# A1-_Ricky_A-Schematic.net
KiCad netlist of a schematic drawn in EAGLE
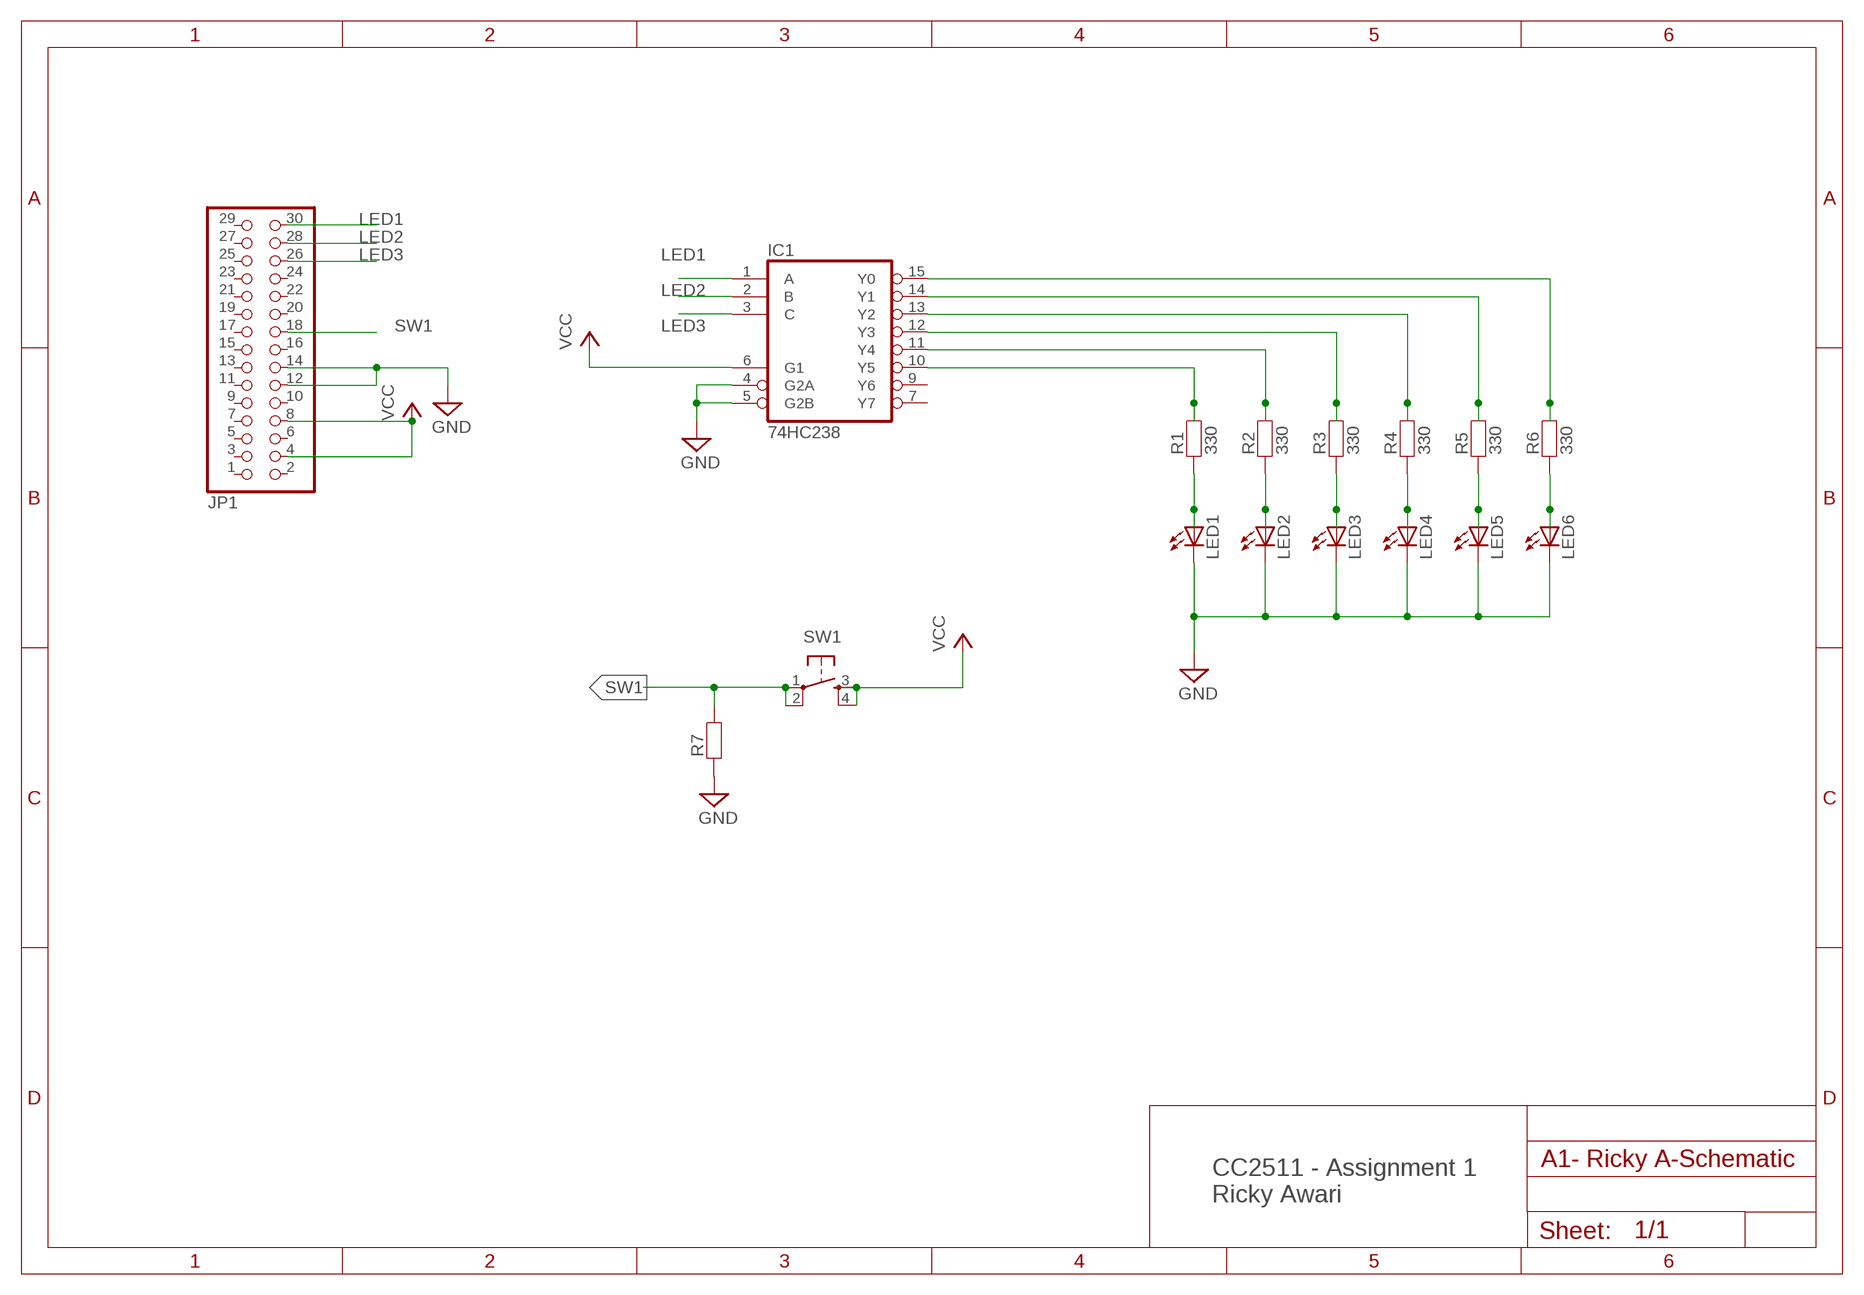
[diagram p0: schematic, sheet 1]

(export (version "E")
  (design (tool "Eeschema 10.0.6"))
  (components
    (comp (ref "IC1")
      (value "74HC238")
      (footprint "eagle-import:DIL16")
      (libsource (lib "eagle-import") (part "74138NHC"))
    )
    (comp (ref "JP1")
      (value "PINHD-2X15")
      (footprint "eagle-import:2X15")
      (libsource (lib "eagle-import") (part "PINHD-2X15"))
    )
    (comp (ref "LED1")
      (value "LED-5MM")
      (footprint "eagle-import:LED-5MM")
      (libsource (lib "eagle-import") (part "LED-5MM"))
    )
    (comp (ref "LED2")
      (value "LED-5MM")
      (footprint "eagle-import:LED-5MM")
      (libsource (lib "eagle-import") (part "LED-5MM"))
    )
    (comp (ref "LED3")
      (value "LED-5MM")
      (footprint "eagle-import:LED-5MM")
      (libsource (lib "eagle-import") (part "LED-5MM"))
    )
    (comp (ref "LED4")
      (value "LED-5MM")
      (footprint "eagle-import:LED-5MM")
      (libsource (lib "eagle-import") (part "LED-5MM"))
    )
    (comp (ref "LED5")
      (value "LED-5MM")
      (footprint "eagle-import:LED-5MM")
      (libsource (lib "eagle-import") (part "LED-5MM"))
    )
    (comp (ref "LED6")
      (value "LED-5MM")
      (footprint "eagle-import:LED-5MM")
      (libsource (lib "eagle-import") (part "LED-5MM"))
    )
    (comp (ref "R1")
      (value "330")
      (footprint "eagle-import:AXIAL-0.4")
      (libsource (lib "eagle-import") (part "RESISTOR-AXIAL-0.4"))
    )
    (comp (ref "R2")
      (value "330")
      (footprint "eagle-import:AXIAL-0.4")
      (libsource (lib "eagle-import") (part "RESISTOR-AXIAL-0.4"))
    )
    (comp (ref "R3")
      (value "330")
      (footprint "eagle-import:AXIAL-0.4")
      (libsource (lib "eagle-import") (part "RESISTOR-AXIAL-0.4"))
    )
    (comp (ref "R4")
      (value "330")
      (footprint "eagle-import:AXIAL-0.4")
      (libsource (lib "eagle-import") (part "RESISTOR-AXIAL-0.4"))
    )
    (comp (ref "R5")
      (value "330")
      (footprint "eagle-import:AXIAL-0.4")
      (libsource (lib "eagle-import") (part "RESISTOR-AXIAL-0.4"))
    )
    (comp (ref "R6")
      (value "330")
      (footprint "eagle-import:AXIAL-0.4")
      (libsource (lib "eagle-import") (part "RESISTOR-AXIAL-0.4"))
    )
    (comp (ref "R7")
      (value "RESISTOR-AXIAL-0.4")
      (footprint "eagle-import:AXIAL-0.4")
      (libsource (lib "eagle-import") (part "RESISTOR-AXIAL-0.4"))
    )
    (comp (ref "SW1")
      (value "TAC_SWITCHPTH")
      (footprint "eagle-import:TACTILE-PTH")
      (libsource (lib "eagle-import") (part "TAC_SWITCHPTH"))
    )
  )
  (nets
    (net (code "1") (name "/LED1") (class "Default")
      (node (ref "IC1") (pin "1") (pinfunction "A_1") (pintype "input"))
      (node (ref "JP1") (pin "30") (pinfunction "30_30") (pintype "passive"))
    )
    (net (code "2") (name "/LED2") (class "Default")
      (node (ref "IC1") (pin "2") (pinfunction "B_2") (pintype "input"))
      (node (ref "JP1") (pin "28") (pinfunction "28_28") (pintype "passive"))
    )
    (net (code "3") (name "/LED3") (class "Default")
      (node (ref "IC1") (pin "3") (pinfunction "C_3") (pintype "input"))
      (node (ref "JP1") (pin "26") (pinfunction "26_26") (pintype "passive"))
    )
    (net (code "4") (name "GND") (class "Default")
      (node (ref "IC1") (pin "4") (pinfunction "G2A_4") (pintype "input"))
      (node (ref "IC1") (pin "5") (pinfunction "G2B_5") (pintype "input"))
      (node (ref "JP1") (pin "12") (pinfunction "12_12") (pintype "passive"))
      (node (ref "JP1") (pin "14") (pinfunction "14_14") (pintype "passive"))
      (node (ref "LED1") (pin "C") (pinfunction "C_C") (pintype "passive"))
      (node (ref "LED2") (pin "C") (pinfunction "C_C") (pintype "passive"))
      (node (ref "LED3") (pin "C") (pinfunction "C_C") (pintype "passive"))
      (node (ref "LED4") (pin "C") (pinfunction "C_C") (pintype "passive"))
      (node (ref "LED5") (pin "C") (pinfunction "C_C") (pintype "passive"))
      (node (ref "LED6") (pin "C") (pinfunction "C_C") (pintype "passive"))
      (node (ref "R7") (pin "P$1") (pinfunction "1_P$1") (pintype "passive"))
    )
    (net (code "5") (name "Net-(IC1A-Y0)") (class "Default")
      (node (ref "IC1") (pin "15") (pinfunction "Y0_15") (pintype "output"))
      (node (ref "R6") (pin "P$2") (pinfunction "2_P$2") (pintype "passive"))
    )
    (net (code "6") (name "Net-(IC1A-Y1)") (class "Default")
      (node (ref "IC1") (pin "14") (pinfunction "Y1_14") (pintype "output"))
      (node (ref "R5") (pin "P$2") (pinfunction "2_P$2") (pintype "passive"))
    )
    (net (code "7") (name "Net-(IC1A-Y2)") (class "Default")
      (node (ref "IC1") (pin "13") (pinfunction "Y2_13") (pintype "output"))
      (node (ref "R4") (pin "P$2") (pinfunction "2_P$2") (pintype "passive"))
    )
    (net (code "8") (name "Net-(IC1A-Y3)") (class "Default")
      (node (ref "IC1") (pin "12") (pinfunction "Y3_12") (pintype "output"))
      (node (ref "R3") (pin "P$2") (pinfunction "2_P$2") (pintype "passive"))
    )
    (net (code "9") (name "Net-(IC1A-Y4)") (class "Default")
      (node (ref "IC1") (pin "11") (pinfunction "Y4_11") (pintype "output"))
      (node (ref "R2") (pin "P$2") (pinfunction "2_P$2") (pintype "passive"))
    )
    (net (code "10") (name "Net-(IC1A-Y5)") (class "Default")
      (node (ref "IC1") (pin "10") (pinfunction "Y5_10") (pintype "output"))
      (node (ref "R1") (pin "P$2") (pinfunction "2_P$2") (pintype "passive"))
    )
    (net (code "11") (name "Net-(R1-1)") (class "Default")
      (node (ref "LED1") (pin "A") (pinfunction "A_A") (pintype "passive"))
      (node (ref "R1") (pin "P$1") (pinfunction "1_P$1") (pintype "passive"))
    )
    (net (code "12") (name "Net-(R2-1)") (class "Default")
      (node (ref "LED2") (pin "A") (pinfunction "A_A") (pintype "passive"))
      (node (ref "R2") (pin "P$1") (pinfunction "1_P$1") (pintype "passive"))
    )
    (net (code "13") (name "Net-(R3-1)") (class "Default")
      (node (ref "LED3") (pin "A") (pinfunction "A_A") (pintype "passive"))
      (node (ref "R3") (pin "P$1") (pinfunction "1_P$1") (pintype "passive"))
    )
    (net (code "14") (name "Net-(R4-1)") (class "Default")
      (node (ref "LED4") (pin "A") (pinfunction "A_A") (pintype "passive"))
      (node (ref "R4") (pin "P$1") (pinfunction "1_P$1") (pintype "passive"))
    )
    (net (code "15") (name "Net-(R5-1)") (class "Default")
      (node (ref "LED5") (pin "A") (pinfunction "A_A") (pintype "passive"))
      (node (ref "R5") (pin "P$1") (pinfunction "1_P$1") (pintype "passive"))
    )
    (net (code "16") (name "Net-(R6-1)") (class "Default")
      (node (ref "LED6") (pin "A") (pinfunction "A_A") (pintype "passive"))
      (node (ref "R6") (pin "P$1") (pinfunction "1_P$1") (pintype "passive"))
    )
    (net (code "17") (name "SW1") (class "Default")
      (node (ref "JP1") (pin "18") (pinfunction "18_18") (pintype "passive"))
      (node (ref "R7") (pin "P$2") (pinfunction "2_P$2") (pintype "passive"))
      (node (ref "SW1") (pin "1") (pinfunction "1_1") (pintype "passive"))
      (node (ref "SW1") (pin "2") (pinfunction "2_2") (pintype "passive"))
    )
    (net (code "18") (name "VCC") (class "Default")
      (node (ref "IC1") (pin "6") (pinfunction "G1_6") (pintype "input"))
      (node (ref "JP1") (pin "4") (pinfunction "4_4") (pintype "passive"))
      (node (ref "JP1") (pin "8") (pinfunction "8_8") (pintype "passive"))
      (node (ref "SW1") (pin "3") (pinfunction "3_3") (pintype "passive"))
      (node (ref "SW1") (pin "4") (pinfunction "4_4") (pintype "passive"))
    )
    (net (code "19") (name "unconnected-(IC1A-Y6-Pad9)") (class "Default")
      (node (ref "IC1") (pin "9") (pinfunction "Y6_9") (pintype "output"))
    )
    (net (code "20") (name "unconnected-(IC1A-Y7-Pad7)") (class "Default")
      (node (ref "IC1") (pin "7") (pinfunction "Y7_7") (pintype "output"))
    )
    (net (code "21") (name "unconnected-(JP1-Pad1)") (class "Default")
      (node (ref "JP1") (pin "1") (pinfunction "1_1") (pintype "passive"))
    )
    (net (code "22") (name "unconnected-(JP1-Pad2)") (class "Default")
      (node (ref "JP1") (pin "2") (pinfunction "2_2") (pintype "passive"))
    )
    (net (code "23") (name "unconnected-(JP1-Pad3)") (class "Default")
      (node (ref "JP1") (pin "3") (pinfunction "3_3") (pintype "passive"))
    )
    (net (code "24") (name "unconnected-(JP1-Pad5)") (class "Default")
      (node (ref "JP1") (pin "5") (pinfunction "5_5") (pintype "passive"))
    )
    (net (code "25") (name "unconnected-(JP1-Pad6)") (class "Default")
      (node (ref "JP1") (pin "6") (pinfunction "6_6") (pintype "passive"))
    )
    (net (code "26") (name "unconnected-(JP1-Pad7)") (class "Default")
      (node (ref "JP1") (pin "7") (pinfunction "7_7") (pintype "passive"))
    )
    (net (code "27") (name "unconnected-(JP1-Pad9)") (class "Default")
      (node (ref "JP1") (pin "9") (pinfunction "9_9") (pintype "passive"))
    )
    (net (code "28") (name "unconnected-(JP1-Pad10)") (class "Default")
      (node (ref "JP1") (pin "10") (pinfunction "10_10") (pintype "passive"))
    )
    (net (code "29") (name "unconnected-(JP1-Pad11)") (class "Default")
      (node (ref "JP1") (pin "11") (pinfunction "11_11") (pintype "passive"))
    )
    (net (code "30") (name "unconnected-(JP1-Pad13)") (class "Default")
      (node (ref "JP1") (pin "13") (pinfunction "13_13") (pintype "passive"))
    )
    (net (code "31") (name "unconnected-(JP1-Pad15)") (class "Default")
      (node (ref "JP1") (pin "15") (pinfunction "15_15") (pintype "passive"))
    )
    (net (code "32") (name "unconnected-(JP1-Pad16)") (class "Default")
      (node (ref "JP1") (pin "16") (pinfunction "16_16") (pintype "passive"))
    )
    (net (code "33") (name "unconnected-(JP1-Pad17)") (class "Default")
      (node (ref "JP1") (pin "17") (pinfunction "17_17") (pintype "passive"))
    )
    (net (code "34") (name "unconnected-(JP1-Pad19)") (class "Default")
      (node (ref "JP1") (pin "19") (pinfunction "19_19") (pintype "passive"))
    )
    (net (code "35") (name "unconnected-(JP1-Pad20)") (class "Default")
      (node (ref "JP1") (pin "20") (pinfunction "20_20") (pintype "passive"))
    )
    (net (code "36") (name "unconnected-(JP1-Pad21)") (class "Default")
      (node (ref "JP1") (pin "21") (pinfunction "21_21") (pintype "passive"))
    )
    (net (code "37") (name "unconnected-(JP1-Pad22)") (class "Default")
      (node (ref "JP1") (pin "22") (pinfunction "22_22") (pintype "passive"))
    )
    (net (code "38") (name "unconnected-(JP1-Pad23)") (class "Default")
      (node (ref "JP1") (pin "23") (pinfunction "23_23") (pintype "passive"))
    )
    (net (code "39") (name "unconnected-(JP1-Pad24)") (class "Default")
      (node (ref "JP1") (pin "24") (pinfunction "24_24") (pintype "passive"))
    )
    (net (code "40") (name "unconnected-(JP1-Pad25)") (class "Default")
      (node (ref "JP1") (pin "25") (pinfunction "25_25") (pintype "passive"))
    )
    (net (code "41") (name "unconnected-(JP1-Pad27)") (class "Default")
      (node (ref "JP1") (pin "27") (pinfunction "27_27") (pintype "passive"))
    )
    (net (code "42") (name "unconnected-(JP1-Pad29)") (class "Default")
      (node (ref "JP1") (pin "29") (pinfunction "29_29") (pintype "passive"))
    )
  )
)
